# ATMEGA2560_Board_V2.net
KiCad netlist of a schematic drawn in EAGLE
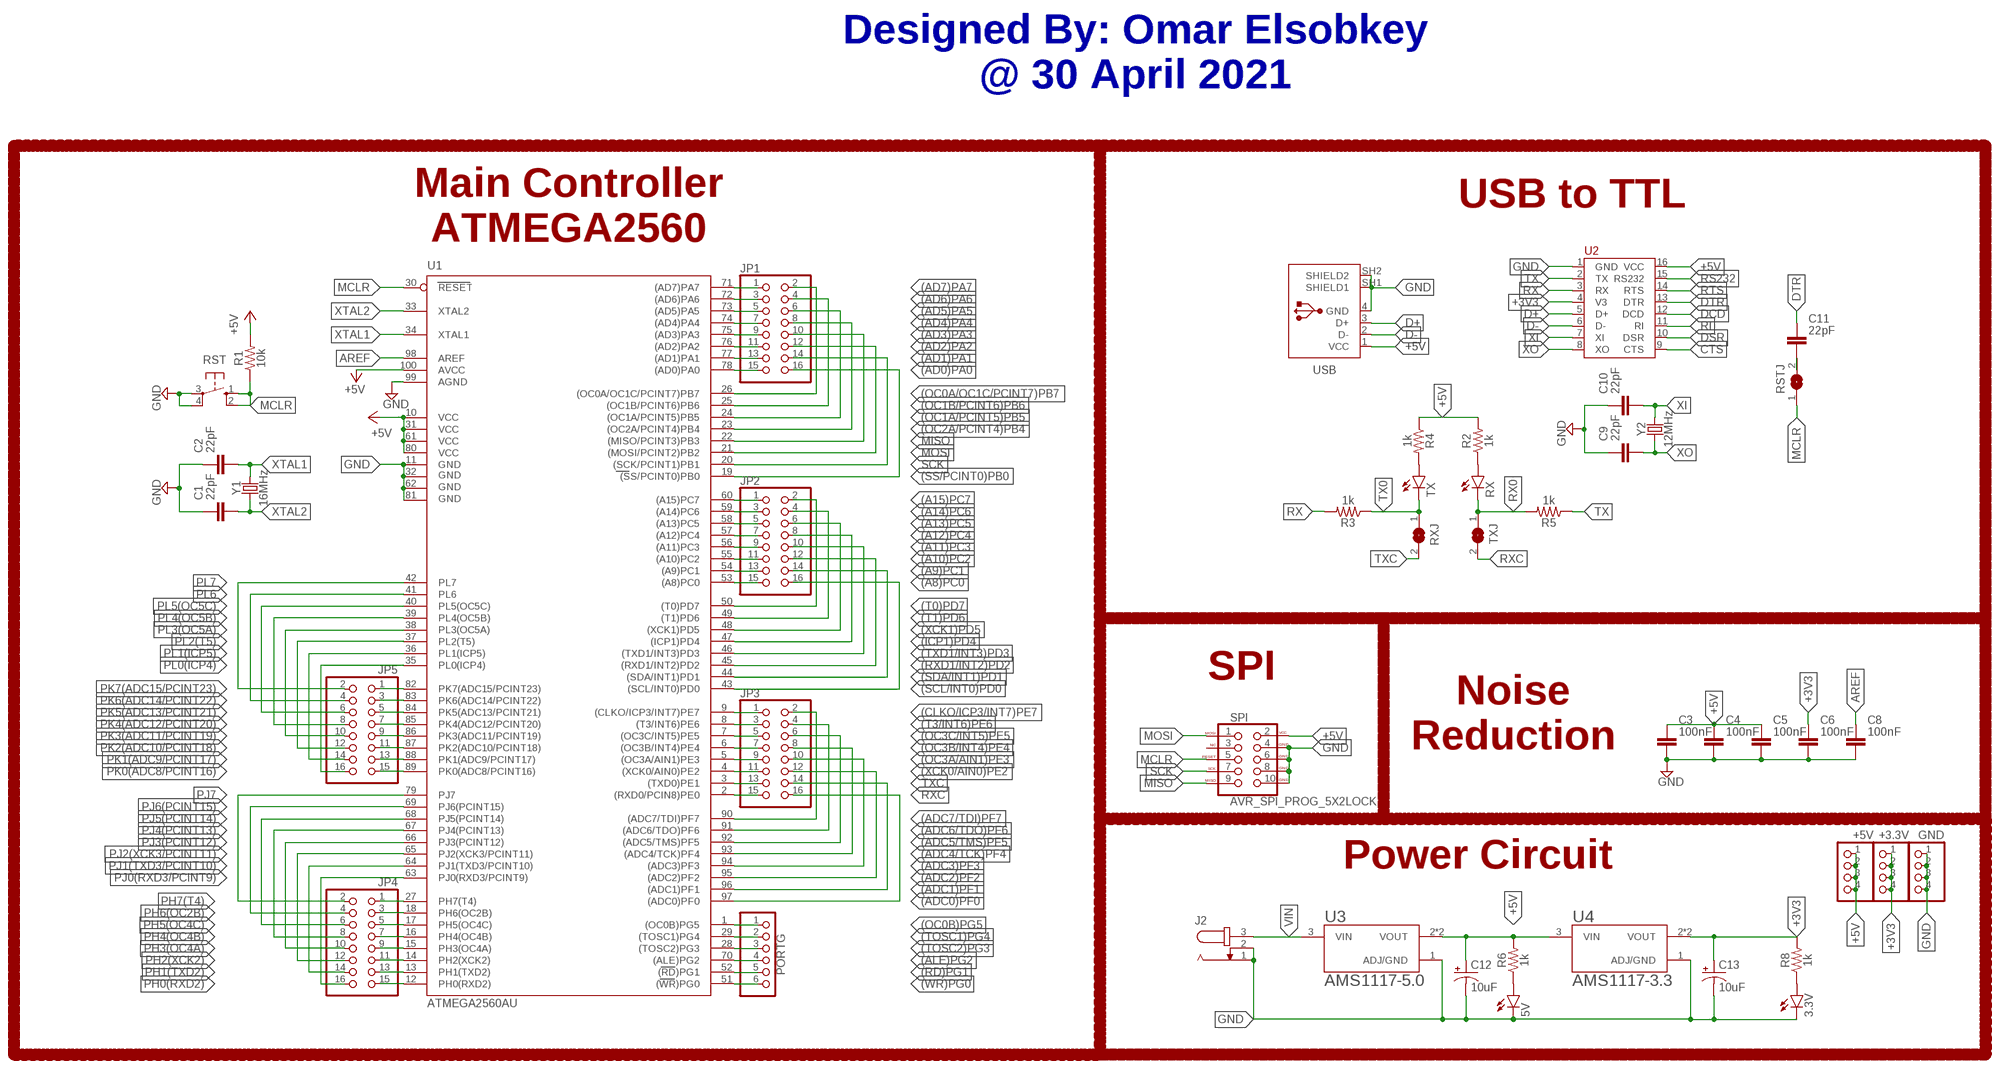
[diagram p0: schematic, sheet 1]

(export (version "E")
  (design (tool "Eeschema 10.0.6"))
  (components
    (comp (ref "+3.3V")
      (value "PINHD-1X4")
      (footprint "eagle-import:1X04")
      (libsource (lib "eagle-import") (part "PINHD-1X4"))
    )
    (comp (ref "+5V")
      (value "PINHD-1X4")
      (footprint "eagle-import:1X04")
      (libsource (lib "eagle-import") (part "PINHD-1X4"))
    )
    (comp (ref "3.3V")
      (value "LEDCHIP-LED0805")
      (footprint "eagle-import:CHIP-LED0805")
      (libsource (lib "eagle-import") (part "LEDCHIP-LED0805"))
    )
    (comp (ref "5V")
      (value "LEDCHIP-LED0805")
      (footprint "eagle-import:CHIP-LED0805")
      (libsource (lib "eagle-import") (part "LEDCHIP-LED0805"))
    )
    (comp (ref "C1")
      (value "22pF")
      (footprint "eagle-import:CAPC2012X110")
      (libsource (lib "eagle-import") (part "CCHIP-0805(2012-METRIC)_"))
    )
    (comp (ref "C2")
      (value "22pF")
      (footprint "eagle-import:CAPC2012X110")
      (libsource (lib "eagle-import") (part "CCHIP-0805(2012-METRIC)_"))
    )
    (comp (ref "C3")
      (value "100nF")
      (footprint "eagle-import:CAPC2012X110")
      (libsource (lib "eagle-import") (part "CCHIP-0805(2012-METRIC)_"))
    )
    (comp (ref "C4")
      (value "100nF")
      (footprint "eagle-import:CAPC2012X110")
      (libsource (lib "eagle-import") (part "CCHIP-0805(2012-METRIC)_"))
    )
    (comp (ref "C5")
      (value "100nF")
      (footprint "eagle-import:CAPC2012X110")
      (libsource (lib "eagle-import") (part "CCHIP-0805(2012-METRIC)_"))
    )
    (comp (ref "C6")
      (value "100nF")
      (footprint "eagle-import:CAPC2012X110")
      (libsource (lib "eagle-import") (part "CCHIP-0805(2012-METRIC)_"))
    )
    (comp (ref "C8")
      (value "100nF")
      (footprint "eagle-import:CAPC2012X110")
      (libsource (lib "eagle-import") (part "CCHIP-0805(2012-METRIC)_"))
    )
    (comp (ref "C9")
      (value "22pF")
      (footprint "eagle-import:CAPC2012X110")
      (libsource (lib "eagle-import") (part "CCHIP-0805(2012-METRIC)_"))
    )
    (comp (ref "C10")
      (value "22pF")
      (footprint "eagle-import:CAPC2012X110")
      (libsource (lib "eagle-import") (part "CCHIP-0805(2012-METRIC)_"))
    )
    (comp (ref "C11")
      (value "22pF")
      (footprint "eagle-import:CAPC2012X110")
      (libsource (lib "eagle-import") (part "CCHIP-0805(2012-METRIC)_"))
    )
    (comp (ref "C12")
      (value "10uF")
      (footprint "eagle-import:CPOL-RADIAL-2.5MM-5MM-KIT")
      (libsource (lib "eagle-import") (part "10UF-POLAR-RADIAL-2.5MM-KIT-25V-20%"))
    )
    (comp (ref "C13")
      (value "10uF")
      (footprint "eagle-import:CPOL-RADIAL-2.5MM-5MM-KIT")
      (libsource (lib "eagle-import") (part "10UF-POLAR-RADIAL-2.5MM-KIT-25V-20%"))
    )
    (comp (ref "GND")
      (value "PINHD-1X4")
      (footprint "eagle-import:1X04")
      (libsource (lib "eagle-import") (part "PINHD-1X4"))
    )
    (comp (ref "J2")
      (value "JACK-PLUG0")
      (footprint "eagle-import:SPC4077")
      (libsource (lib "eagle-import") (part "JACK-PLUG0"))
    )
    (comp (ref "JP1")
      (value "PINHD-2X8")
      (footprint "eagle-import:2X08")
      (libsource (lib "eagle-import") (part "PINHD-2X8"))
    )
    (comp (ref "JP2")
      (value "PINHD-2X8")
      (footprint "eagle-import:2X08")
      (libsource (lib "eagle-import") (part "PINHD-2X8"))
    )
    (comp (ref "JP3")
      (value "PINHD-2X8")
      (footprint "eagle-import:2X08")
      (libsource (lib "eagle-import") (part "PINHD-2X8"))
    )
    (comp (ref "JP4")
      (value "PINHD-2X8")
      (footprint "eagle-import:2X08")
      (libsource (lib "eagle-import") (part "PINHD-2X8"))
    )
    (comp (ref "JP5")
      (value "PINHD-2X8")
      (footprint "eagle-import:2X08")
      (libsource (lib "eagle-import") (part "PINHD-2X8"))
    )
    (comp (ref "PORTG")
      (value "PINHD-1X6")
      (footprint "eagle-import:1X06")
      (libsource (lib "eagle-import") (part "PINHD-1X6"))
    )
    (comp (ref "R1")
      (value "10k")
      (footprint "eagle-import:1206")
      (libsource (lib "eagle-import") (part "RESISTOR1206"))
    )
    (comp (ref "R2")
      (value "1k")
      (footprint "eagle-import:1206")
      (libsource (lib "eagle-import") (part "RESISTOR1206"))
    )
    (comp (ref "R3")
      (value "1k")
      (footprint "eagle-import:1206")
      (libsource (lib "eagle-import") (part "RESISTOR1206"))
    )
    (comp (ref "R4")
      (value "1k")
      (footprint "eagle-import:1206")
      (libsource (lib "eagle-import") (part "RESISTOR1206"))
    )
    (comp (ref "R5")
      (value "1k")
      (footprint "eagle-import:1206")
      (libsource (lib "eagle-import") (part "RESISTOR1206"))
    )
    (comp (ref "R6")
      (value "1k")
      (footprint "eagle-import:1206")
      (libsource (lib "eagle-import") (part "RESISTOR1206"))
    )
    (comp (ref "R8")
      (value "1k")
      (footprint "eagle-import:1206")
      (libsource (lib "eagle-import") (part "RESISTOR1206"))
    )
    (comp (ref "RST")
      (value "10-XX")
      (footprint "eagle-import:B3F-10XX")
      (fields (field (name "MPN") "B3F-1000"))
      (libsource (lib "eagle-import") (part "10-XX"))
    )
    (comp (ref "RSTJ")
      (value "SJW")
      (footprint "eagle-import:SJW")
      (libsource (lib "eagle-import") (part "SJW"))
    )
    (comp (ref "RX")
      (value "LEDCHIP-LED0805")
      (footprint "eagle-import:CHIP-LED0805")
      (libsource (lib "eagle-import") (part "LEDCHIP-LED0805"))
    )
    (comp (ref "RXJ")
      (value "SJW")
      (footprint "eagle-import:SJW")
      (libsource (lib "eagle-import") (part "SJW"))
    )
    (comp (ref "SPI")
      (value "AVR_SPI_PROG_5X2LOCK")
      (footprint "eagle-import:2X5-SHROUDED_LOCK")
      (libsource (lib "eagle-import") (part "AVR_SPI_PROG_5X2LOCK"))
    )
    (comp (ref "TX")
      (value "LEDCHIP-LED0805")
      (footprint "eagle-import:CHIP-LED0805")
      (libsource (lib "eagle-import") (part "LEDCHIP-LED0805"))
    )
    (comp (ref "TXJ")
      (value "SJW")
      (footprint "eagle-import:SJW")
      (libsource (lib "eagle-import") (part "SJW"))
    )
    (comp (ref "U1")
      (value "ATMEGA2560AU")
      (footprint "eagle-import:TQFP100")
      (libsource (lib "eagle-import") (part "ATMEGA2560AU"))
    )
    (comp (ref "U2")
      (value "CH340G")
      (footprint "eagle-import:SOP-16")
      (libsource (lib "eagle-import") (part "CH340G"))
    )
    (comp (ref "U3")
      (value "AMS1117-5.0")
      (footprint "eagle-import:AMS1117-5.0")
      (fields (field (name "MF") "Advanced Monolithic Systems"))
      (libsource (lib "eagle-import") (part "AMS1117-5.0"))
    )
    (comp (ref "U4")
      (value "AMS1117-3.3")
      (footprint "eagle-import:AMS1117-5.0")
      (fields (field (name "MF") "Advanced Monolithic Systems") (field (name "MP") "AMS1117-5.0"))
      (libsource (lib "eagle-import") (part "AMS1117-5.0"))
    )
    (comp (ref "USB")
      (value "61729-1011")
      (footprint "eagle-import:61729-1011BLF")
      (fields (field (name "MANUFACTURER") "Amphenol ICC (FCI)") (field (name "MPN") "61729-1011BLF"))
      (libsource (lib "eagle-import") (part "61729-1011"))
    )
    (comp (ref "Y1")
      (value "16MHz")
      (footprint "eagle-import:HC49U")
      (libsource (lib "eagle-import") (part "CRYSTALPTH-HC49UV"))
    )
    (comp (ref "Y2")
      (value "12MHz")
      (footprint "eagle-import:HC49U")
      (libsource (lib "eagle-import") (part "CRYSTALPTH-HC49UV"))
    )
  )
  (nets
    (net (code "1") (name "(A8)PC0") (class "Default")
      (node (ref "JP2") (pin "15") (pinfunction "15_15") (pintype "passive"))
      (node (ref "U1") (pin "53") (pinfunction "(A8)PC0_53") (pintype "bidirectional"))
    )
    (net (code "2") (name "(A9)PC1") (class "Default")
      (node (ref "JP2") (pin "13") (pinfunction "13_13") (pintype "passive"))
      (node (ref "U1") (pin "54") (pinfunction "(A9)PC1_54") (pintype "bidirectional"))
    )
    (net (code "3") (name "(A10)PC2") (class "Default")
      (node (ref "JP2") (pin "11") (pinfunction "11_11") (pintype "passive"))
      (node (ref "U1") (pin "55") (pinfunction "(A10)PC2_55") (pintype "bidirectional"))
    )
    (net (code "4") (name "(A11)PC3") (class "Default")
      (node (ref "JP2") (pin "9") (pinfunction "9_9") (pintype "passive"))
      (node (ref "U1") (pin "56") (pinfunction "(A11)PC3_56") (pintype "bidirectional"))
    )
    (net (code "5") (name "(A12)PC4") (class "Default")
      (node (ref "JP2") (pin "7") (pinfunction "7_7") (pintype "passive"))
      (node (ref "U1") (pin "57") (pinfunction "(A12)PC4_57") (pintype "bidirectional"))
    )
    (net (code "6") (name "(A13)PC5") (class "Default")
      (node (ref "JP2") (pin "5") (pinfunction "5_5") (pintype "passive"))
      (node (ref "U1") (pin "58") (pinfunction "(A13)PC5_58") (pintype "bidirectional"))
    )
    (net (code "7") (name "(A14)PC6") (class "Default")
      (node (ref "JP2") (pin "3") (pinfunction "3_3") (pintype "passive"))
      (node (ref "U1") (pin "59") (pinfunction "(A14)PC6_59") (pintype "bidirectional"))
    )
    (net (code "8") (name "(A15)PC7") (class "Default")
      (node (ref "JP2") (pin "1") (pinfunction "1_1") (pintype "passive"))
      (node (ref "U1") (pin "60") (pinfunction "(A15)PC7_60") (pintype "bidirectional"))
    )
    (net (code "9") (name "(AD0)PA0") (class "Default")
      (node (ref "JP1") (pin "15") (pinfunction "15_15") (pintype "passive"))
      (node (ref "U1") (pin "78") (pinfunction "(AD0)PA0_78") (pintype "bidirectional"))
    )
    (net (code "10") (name "(AD1)PA1") (class "Default")
      (node (ref "JP1") (pin "13") (pinfunction "13_13") (pintype "passive"))
      (node (ref "U1") (pin "77") (pinfunction "(AD1)PA1_77") (pintype "bidirectional"))
    )
    (net (code "11") (name "(AD2)PA2") (class "Default")
      (node (ref "JP1") (pin "11") (pinfunction "11_11") (pintype "passive"))
      (node (ref "U1") (pin "76") (pinfunction "(AD2)PA2_76") (pintype "bidirectional"))
    )
    (net (code "12") (name "(AD3)PA3") (class "Default")
      (node (ref "JP1") (pin "9") (pinfunction "9_9") (pintype "passive"))
      (node (ref "U1") (pin "75") (pinfunction "(AD3)PA3_75") (pintype "bidirectional"))
    )
    (net (code "13") (name "(AD4)PA4") (class "Default")
      (node (ref "JP1") (pin "7") (pinfunction "7_7") (pintype "passive"))
      (node (ref "U1") (pin "74") (pinfunction "(AD4)PA4_74") (pintype "bidirectional"))
    )
    (net (code "14") (name "(AD5)PA5") (class "Default")
      (node (ref "JP1") (pin "5") (pinfunction "5_5") (pintype "passive"))
      (node (ref "U1") (pin "73") (pinfunction "(AD5)PA5_73") (pintype "bidirectional"))
    )
    (net (code "15") (name "(AD6)PA6") (class "Default")
      (node (ref "JP1") (pin "3") (pinfunction "3_3") (pintype "passive"))
      (node (ref "U1") (pin "72") (pinfunction "(AD6)PA6_72") (pintype "bidirectional"))
    )
    (net (code "16") (name "(AD7)PA7") (class "Default")
      (node (ref "JP1") (pin "1") (pinfunction "1_1") (pintype "passive"))
      (node (ref "U1") (pin "71") (pinfunction "(AD7)PA7_71") (pintype "bidirectional"))
    )
    (net (code "17") (name "(ADC0)PF0") (class "Default")
      (node (ref "JP3") (pin "16") (pinfunction "16_16") (pintype "passive"))
      (node (ref "U1") (pin "97") (pinfunction "(ADC0)PF0_97") (pintype "bidirectional"))
    )
    (net (code "18") (name "(ADC1)PF1") (class "Default")
      (node (ref "JP3") (pin "14") (pinfunction "14_14") (pintype "passive"))
      (node (ref "U1") (pin "96") (pinfunction "(ADC1)PF1_96") (pintype "bidirectional"))
    )
    (net (code "19") (name "(ADC2)PF2") (class "Default")
      (node (ref "JP3") (pin "12") (pinfunction "12_12") (pintype "passive"))
      (node (ref "U1") (pin "95") (pinfunction "(ADC2)PF2_95") (pintype "bidirectional"))
    )
    (net (code "20") (name "(ADC3)PF3") (class "Default")
      (node (ref "JP3") (pin "10") (pinfunction "10_10") (pintype "passive"))
      (node (ref "U1") (pin "94") (pinfunction "(ADC3)PF3_94") (pintype "bidirectional"))
    )
    (net (code "21") (name "(ADC4{slash}TCK)PF4") (class "Default")
      (node (ref "JP3") (pin "8") (pinfunction "8_8") (pintype "passive"))
      (node (ref "U1") (pin "93") (pinfunction "(ADC4/TCK)PF4_93") (pintype "bidirectional"))
    )
    (net (code "22") (name "(ADC5{slash}TMS)PF5") (class "Default")
      (node (ref "JP3") (pin "6") (pinfunction "6_6") (pintype "passive"))
      (node (ref "U1") (pin "92") (pinfunction "(ADC5/TMS)PF5_92") (pintype "bidirectional"))
    )
    (net (code "23") (name "(ADC6{slash}TDO)PF6") (class "Default")
      (node (ref "JP3") (pin "4") (pinfunction "4_4") (pintype "passive"))
      (node (ref "U1") (pin "91") (pinfunction "(ADC6/TDO)PF6_91") (pintype "bidirectional"))
    )
    (net (code "24") (name "(ADC7{slash}TDI)PF7") (class "Default")
      (node (ref "JP3") (pin "2") (pinfunction "2_2") (pintype "passive"))
      (node (ref "U1") (pin "90") (pinfunction "(ADC7/TDI)PF7_90") (pintype "bidirectional"))
    )
    (net (code "25") (name "(ALE)PG2") (class "Default")
      (node (ref "PORTG") (pin "4") (pinfunction "4_4") (pintype "passive"))
      (node (ref "U1") (pin "70") (pinfunction "(ALE)PG2_70") (pintype "bidirectional"))
    )
    (net (code "26") (name "(CLKO{slash}ICP3{slash}INT7)PE7") (class "Default")
      (node (ref "JP3") (pin "1") (pinfunction "1_1") (pintype "passive"))
      (node (ref "U1") (pin "9") (pinfunction "(CLKO/ICP3/INT7)PE7_9") (pintype "bidirectional"))
    )
    (net (code "27") (name "(ICP1)PD4") (class "Default")
      (node (ref "JP2") (pin "8") (pinfunction "8_8") (pintype "passive"))
      (node (ref "U1") (pin "47") (pinfunction "(ICP1)PD4_47") (pintype "bidirectional"))
    )
    (net (code "28") (name "(OC0A{slash}OC1C{slash}PCINT7)PB7") (class "Default")
      (node (ref "JP1") (pin "2") (pinfunction "2_2") (pintype "passive"))
      (node (ref "U1") (pin "26") (pinfunction "(OC0A/OC1C/PCINT7)PB7_26") (pintype "bidirectional"))
    )
    (net (code "29") (name "(OC0B)PG5") (class "Default")
      (node (ref "PORTG") (pin "1") (pinfunction "1_1") (pintype "passive"))
      (node (ref "U1") (pin "1") (pinfunction "(OC0B)PG5_1") (pintype "bidirectional"))
    )
    (net (code "30") (name "(OC1A{slash}PCINT5)PB5") (class "Default")
      (node (ref "JP1") (pin "6") (pinfunction "6_6") (pintype "passive"))
      (node (ref "U1") (pin "24") (pinfunction "(OC1A/PCINT5)PB5_24") (pintype "bidirectional"))
    )
    (net (code "31") (name "(OC1B{slash}PCINT6)PB6") (class "Default")
      (node (ref "JP1") (pin "4") (pinfunction "4_4") (pintype "passive"))
      (node (ref "U1") (pin "25") (pinfunction "(OC1B/PCINT6)PB6_25") (pintype "bidirectional"))
    )
    (net (code "32") (name "(OC2A{slash}PCINT4)PB4") (class "Default")
      (node (ref "JP1") (pin "8") (pinfunction "8_8") (pintype "passive"))
      (node (ref "U1") (pin "23") (pinfunction "(OC2A/PCINT4)PB4_23") (pintype "bidirectional"))
    )
    (net (code "33") (name "(OC3A{slash}AIN1)PE3") (class "Default")
      (node (ref "JP3") (pin "9") (pinfunction "9_9") (pintype "passive"))
      (node (ref "U1") (pin "5") (pinfunction "(OC3A/AIN1)PE3_5") (pintype "bidirectional"))
    )
    (net (code "34") (name "(OC3B{slash}INT4)PE4") (class "Default")
      (node (ref "JP3") (pin "7") (pinfunction "7_7") (pintype "passive"))
      (node (ref "U1") (pin "6") (pinfunction "(OC3B/INT4)PE4_6") (pintype "bidirectional"))
    )
    (net (code "35") (name "(OC3C{slash}INT5)PE5") (class "Default")
      (node (ref "JP3") (pin "5") (pinfunction "5_5") (pintype "passive"))
      (node (ref "U1") (pin "7") (pinfunction "(OC3C/INT5)PE5_7") (pintype "bidirectional"))
    )
    (net (code "36") (name "(RD)PG1") (class "Default")
      (node (ref "PORTG") (pin "5") (pinfunction "5_5") (pintype "passive"))
      (node (ref "U1") (pin "52") (pinfunction "(RD)PG1_52") (pintype "bidirectional"))
    )
    (net (code "37") (name "(RXD1{slash}INT2)PD2") (class "Default")
      (node (ref "JP2") (pin "12") (pinfunction "12_12") (pintype "passive"))
      (node (ref "U1") (pin "45") (pinfunction "(RXD1/INT2)PD2_45") (pintype "bidirectional"))
    )
    (net (code "38") (name "(SCL{slash}INT0)PD0") (class "Default")
      (node (ref "JP2") (pin "16") (pinfunction "16_16") (pintype "passive"))
      (node (ref "U1") (pin "43") (pinfunction "(SCL/INT0)PD0_43") (pintype "bidirectional"))
    )
    (net (code "39") (name "(SDA{slash}INT1)PD1") (class "Default")
      (node (ref "JP2") (pin "14") (pinfunction "14_14") (pintype "passive"))
      (node (ref "U1") (pin "44") (pinfunction "(SDA/INT1)PD1_44") (pintype "bidirectional"))
    )
    (net (code "40") (name "(SS{slash}PCINT0)PB0") (class "Default")
      (node (ref "JP1") (pin "16") (pinfunction "16_16") (pintype "passive"))
      (node (ref "U1") (pin "19") (pinfunction "(SS/PCINT0)PB0_19") (pintype "bidirectional"))
    )
    (net (code "41") (name "(T0)PD7") (class "Default")
      (node (ref "JP2") (pin "2") (pinfunction "2_2") (pintype "passive"))
      (node (ref "U1") (pin "50") (pinfunction "(T0)PD7_50") (pintype "bidirectional"))
    )
    (net (code "42") (name "(T1)PD6") (class "Default")
      (node (ref "JP2") (pin "4") (pinfunction "4_4") (pintype "passive"))
      (node (ref "U1") (pin "49") (pinfunction "(T1)PD6_49") (pintype "bidirectional"))
    )
    (net (code "43") (name "(T3{slash}INT6)PE6") (class "Default")
      (node (ref "JP3") (pin "3") (pinfunction "3_3") (pintype "passive"))
      (node (ref "U1") (pin "8") (pinfunction "(T3/INT6)PE6_8") (pintype "bidirectional"))
    )
    (net (code "44") (name "(TOSC1)PG4") (class "Default")
      (node (ref "PORTG") (pin "2") (pinfunction "2_2") (pintype "passive"))
      (node (ref "U1") (pin "29") (pinfunction "(TOSC1)PG4_29") (pintype "bidirectional"))
    )
    (net (code "45") (name "(TOSC2)PG3") (class "Default")
      (node (ref "PORTG") (pin "3") (pinfunction "3_3") (pintype "passive"))
      (node (ref "U1") (pin "28") (pinfunction "(TOSC2)PG3_28") (pintype "bidirectional"))
    )
    (net (code "46") (name "(TXD1{slash}INT3)PD3") (class "Default")
      (node (ref "JP2") (pin "10") (pinfunction "10_10") (pintype "passive"))
      (node (ref "U1") (pin "46") (pinfunction "(TXD1/INT3)PD3_46") (pintype "bidirectional"))
    )
    (net (code "47") (name "(WR)PG0") (class "Default")
      (node (ref "PORTG") (pin "6") (pinfunction "6_6") (pintype "passive"))
      (node (ref "U1") (pin "51") (pinfunction "(WR)PG0_51") (pintype "bidirectional"))
    )
    (net (code "48") (name "(XCK0{slash}AIN0)PE2") (class "Default")
      (node (ref "JP3") (pin "11") (pinfunction "11_11") (pintype "passive"))
      (node (ref "U1") (pin "4") (pinfunction "(XCK0/AIN0)PE2_4") (pintype "bidirectional"))
    )
    (net (code "49") (name "(XCK1)PD5") (class "Default")
      (node (ref "JP2") (pin "6") (pinfunction "6_6") (pintype "passive"))
      (node (ref "U1") (pin "48") (pinfunction "(XCK1)PD5_48") (pintype "bidirectional"))
    )
    (net (code "50") (name "+3V3") (class "Default")
      (node (ref "+3.3V") (pin "1") (pinfunction "1_1") (pintype "passive"))
      (node (ref "+3.3V") (pin "2") (pinfunction "2_2") (pintype "passive"))
      (node (ref "+3.3V") (pin "3") (pinfunction "3_3") (pintype "passive"))
      (node (ref "+3.3V") (pin "4") (pinfunction "4_4") (pintype "passive"))
      (node (ref "C13") (pin "1") (pinfunction "+_1") (pintype "passive"))
      (node (ref "C6") (pin "1") (pinfunction "1_1") (pintype "passive"))
      (node (ref "R8") (pin "2") (pinfunction "2_2") (pintype "passive"))
      (node (ref "U2") (pin "4") (pinfunction "V3_4") (pintype "bidirectional"))
      (node (ref "U4") (pin "2") (pinfunction "VOUT_2") (pintype "output"))
      (node (ref "U4") (pin "4") (pinfunction "VOUT_4") (pintype "output"))
    )
    (net (code "51") (name "+5V") (class "Default")
      (node (ref "+5V") (pin "1") (pinfunction "1_1") (pintype "passive"))
      (node (ref "+5V") (pin "2") (pinfunction "2_2") (pintype "passive"))
      (node (ref "+5V") (pin "3") (pinfunction "3_3") (pintype "passive"))
      (node (ref "+5V") (pin "4") (pinfunction "4_4") (pintype "passive"))
      (node (ref "C12") (pin "1") (pinfunction "+_1") (pintype "passive"))
      (node (ref "C3") (pin "1") (pinfunction "1_1") (pintype "passive"))
      (node (ref "C4") (pin "1") (pinfunction "1_1") (pintype "passive"))
      (node (ref "C5") (pin "1") (pinfunction "1_1") (pintype "passive"))
      (node (ref "R1") (pin "2") (pinfunction "2_2") (pintype "passive"))
      (node (ref "R2") (pin "2") (pinfunction "2_2") (pintype "passive"))
      (node (ref "R4") (pin "1") (pinfunction "1_1") (pintype "passive"))
      (node (ref "R6") (pin "2") (pinfunction "2_2") (pintype "passive"))
      (node (ref "SPI") (pin "2") (pinfunction "VCC_2") (pintype "power_in"))
      (node (ref "U1") (pin "10") (pinfunction "VCC_10") (pintype "power_in"))
      (node (ref "U1") (pin "100") (pinfunction "AVCC_100") (pintype "power_in"))
      (node (ref "U1") (pin "31") (pinfunction "VCC1_31") (pintype "power_in"))
      (node (ref "U1") (pin "61") (pinfunction "VCC2_61") (pintype "power_in"))
      (node (ref "U1") (pin "80") (pinfunction "VCC3_80") (pintype "power_in"))
      (node (ref "U2") (pin "16") (pinfunction "VCC_16") (pintype "bidirectional"))
      (node (ref "U3") (pin "2") (pinfunction "VOUT_2") (pintype "output"))
      (node (ref "U3") (pin "4") (pinfunction "VOUT_4") (pintype "output"))
      (node (ref "U4") (pin "3") (pinfunction "VIN_3") (pintype "input"))
      (node (ref "USB") (pin "1") (pinfunction "VCC_1") (pintype "power_in"))
    )
    (net (code "52") (name "AREF") (class "Default")
      (node (ref "C8") (pin "1") (pinfunction "1_1") (pintype "passive"))
      (node (ref "U1") (pin "98") (pinfunction "AREF_98") (pintype "bidirectional"))
    )
    (net (code "53") (name "CTS") (class "Default")
      (node (ref "U2") (pin "9") (pinfunction "CTS_9") (pintype "bidirectional"))
    )
    (net (code "54") (name "D+") (class "Default")
      (node (ref "U2") (pin "5") (pinfunction "D+_5") (pintype "bidirectional"))
      (node (ref "USB") (pin "3") (pinfunction "D+_3") (pintype "bidirectional"))
    )
    (net (code "55") (name "D-") (class "Default")
      (node (ref "U2") (pin "6") (pinfunction "D-_6") (pintype "bidirectional"))
      (node (ref "USB") (pin "2") (pinfunction "D-_2") (pintype "bidirectional"))
    )
    (net (code "56") (name "DCD") (class "Default")
      (node (ref "U2") (pin "12") (pinfunction "DCD_12") (pintype "bidirectional"))
    )
    (net (code "57") (name "DSR") (class "Default")
      (node (ref "U2") (pin "10") (pinfunction "DSR_10") (pintype "bidirectional"))
    )
    (net (code "58") (name "DTR") (class "Default")
      (node (ref "C11") (pin "1") (pinfunction "1_1") (pintype "passive"))
      (node (ref "U2") (pin "13") (pinfunction "DTR_13") (pintype "bidirectional"))
    )
    (net (code "59") (name "GND") (class "Default")
      (node (ref "3.3V") (pin "C") (pinfunction "C_C") (pintype "passive"))
      (node (ref "5V") (pin "C") (pinfunction "C_C") (pintype "passive"))
      (node (ref "C1") (pin "1") (pinfunction "1_1") (pintype "passive"))
      (node (ref "C10") (pin "1") (pinfunction "1_1") (pintype "passive"))
      (node (ref "C12") (pin "2") (pinfunction "-_2") (pintype "passive"))
      (node (ref "C13") (pin "2") (pinfunction "-_2") (pintype "passive"))
      (node (ref "C2") (pin "1") (pinfunction "1_1") (pintype "passive"))
      (node (ref "C3") (pin "2") (pinfunction "2_2") (pintype "passive"))
      (node (ref "C4") (pin "2") (pinfunction "2_2") (pintype "passive"))
      (node (ref "C5") (pin "2") (pinfunction "2_2") (pintype "passive"))
      (node (ref "C6") (pin "2") (pinfunction "2_2") (pintype "passive"))
      (node (ref "C8") (pin "2") (pinfunction "2_2") (pintype "passive"))
      (node (ref "C9") (pin "1") (pinfunction "1_1") (pintype "passive"))
      (node (ref "GND") (pin "1") (pinfunction "1_1") (pintype "passive"))
      (node (ref "GND") (pin "2") (pinfunction "2_2") (pintype "passive"))
      (node (ref "GND") (pin "3") (pinfunction "3_3") (pintype "passive"))
      (node (ref "GND") (pin "4") (pinfunction "4_4") (pintype "passive"))
      (node (ref "J2") (pin "1") (pinfunction "1_1") (pintype "passive"))
      (node (ref "J2") (pin "2") (pinfunction "2_2") (pintype "passive"))
      (node (ref "RST") (pin "3") (pinfunction "P_3") (pintype "passive"))
      (node (ref "RST") (pin "4") (pinfunction "P1_4") (pintype "passive"))
      (node (ref "SPI") (pin "10") (pinfunction "GND_10") (pintype "power_in"))
      (node (ref "SPI") (pin "4") (pinfunction "GND_4") (pintype "power_in"))
      (node (ref "SPI") (pin "6") (pinfunction "GND_6") (pintype "power_in"))
      (node (ref "SPI") (pin "8") (pinfunction "GND_8") (pintype "power_in"))
      (node (ref "U1") (pin "11") (pinfunction "GND_11") (pintype "power_in"))
      (node (ref "U1") (pin "32") (pinfunction "GND1_32") (pintype "power_in"))
      (node (ref "U1") (pin "62") (pinfunction "GND2_62") (pintype "power_in"))
      (node (ref "U1") (pin "81") (pinfunction "GND3_81") (pintype "power_in"))
      (node (ref "U1") (pin "99") (pinfunction "AGND_99") (pintype "power_in"))
      (node (ref "U2") (pin "1") (pinfunction "GND_1") (pintype "bidirectional"))
      (node (ref "U3") (pin "1") (pinfunction "ADJ/GND_1") (pintype "power_in"))
      (node (ref "U4") (pin "1") (pinfunction "ADJ/GND_1") (pintype "power_in"))
      (node (ref "USB") (pin "4") (pinfunction "GND_4") (pintype "power_in"))
      (node (ref "USB") (pin "SH1") (pinfunction "SHIELD1_SH1") (pintype "power_in"))
      (node (ref "USB") (pin "SH2") (pinfunction "SHIELD2_SH2") (pintype "power_in"))
    )
    (net (code "60") (name "MCLR") (class "Default")
      (node (ref "R1") (pin "1") (pinfunction "1_1") (pintype "passive"))
      (node (ref "RST") (pin "1") (pinfunction "S_1") (pintype "passive"))
      (node (ref "RST") (pin "2") (pinfunction "S1_2") (pintype "passive"))
      (node (ref "RSTJ") (pin "1") (pinfunction "1_1") (pintype "passive"))
      (node (ref "SPI") (pin "5") (pinfunction "RESET_5") (pintype "passive"))
      (node (ref "U1") (pin "30") (pinfunction "RESET_30") (pintype "input"))
    )
    (net (code "61") (name "MISO") (class "Default")
      (node (ref "JP1") (pin "10") (pinfunction "10_10") (pintype "passive"))
      (node (ref "SPI") (pin "9") (pinfunction "MISO_9") (pintype "passive"))
      (node (ref "U1") (pin "22") (pinfunction "(MISO/PCINT3)PB3_22") (pintype "bidirectional"))
    )
    (net (code "62") (name "MOSI") (class "Default")
      (node (ref "JP1") (pin "12") (pinfunction "12_12") (pintype "passive"))
      (node (ref "SPI") (pin "1") (pinfunction "MOSI_1") (pintype "passive"))
      (node (ref "U1") (pin "21") (pinfunction "(MOSI/PCINT2)PB2_21") (pintype "bidirectional"))
    )
    (net (code "63") (name "Net-(3.3V-PadA)") (class "Default")
      (node (ref "3.3V") (pin "A") (pinfunction "A_A") (pintype "passive"))
      (node (ref "R8") (pin "1") (pinfunction "1_1") (pintype "passive"))
    )
    (net (code "64") (name "Net-(5V-PadA)") (class "Default")
      (node (ref "5V") (pin "A") (pinfunction "A_A") (pintype "passive"))
      (node (ref "R6") (pin "1") (pinfunction "1_1") (pintype "passive"))
    )
    (net (code "65") (name "Net-(C11-Pad2)") (class "Default")
      (node (ref "C11") (pin "2") (pinfunction "2_2") (pintype "passive"))
      (node (ref "RSTJ") (pin "2") (pinfunction "2_2") (pintype "passive"))
    )
    (net (code "66") (name "Net-(R2-Pad1)") (class "Default")
      (node (ref "R2") (pin "1") (pinfunction "1_1") (pintype "passive"))
      (node (ref "RX") (pin "A") (pinfunction "A_A") (pintype "passive"))
    )
    (net (code "67") (name "Net-(R4-Pad2)") (class "Default")
      (node (ref "R4") (pin "2") (pinfunction "2_2") (pintype "passive"))
      (node (ref "TX") (pin "A") (pinfunction "A_A") (pintype "passive"))
    )
    (net (code "68") (name "PH0(RXD2)") (class "Default")
      (node (ref "JP4") (pin "15") (pinfunction "15_15") (pintype "passive"))
      (node (ref "U1") (pin "12") (pinfunction "PH0(RXD2)_12") (pintype "bidirectional"))
    )
    (net (code "69") (name "PH1(TXD2)") (class "Default")
      (node (ref "JP4") (pin "13") (pinfunction "13_13") (pintype "passive"))
      (node (ref "U1") (pin "13") (pinfunction "PH1(TXD2)_13") (pintype "bidirectional"))
    )
    (net (code "70") (name "PH2(XCK2)") (class "Default")
      (node (ref "JP4") (pin "11") (pinfunction "11_11") (pintype "passive"))
      (node (ref "U1") (pin "14") (pinfunction "PH2(XCK2)_14") (pintype "bidirectional"))
    )
    (net (code "71") (name "PH3(OC4A)") (class "Default")
      (node (ref "JP4") (pin "9") (pinfunction "9_9") (pintype "passive"))
      (node (ref "U1") (pin "15") (pinfunction "PH3(OC4A)_15") (pintype "bidirectional"))
    )
    (net (code "72") (name "PH4(OC4B)") (class "Default")
      (node (ref "JP4") (pin "7") (pinfunction "7_7") (pintype "passive"))
      (node (ref "U1") (pin "16") (pinfunction "PH4(OC4B)_16") (pintype "bidirectional"))
    )
    (net (code "73") (name "PH5(OC4C)") (class "Default")
      (node (ref "JP4") (pin "5") (pinfunction "5_5") (pintype "passive"))
      (node (ref "U1") (pin "17") (pinfunction "PH5(OC4C)_17") (pintype "bidirectional"))
    )
    (net (code "74") (name "PH6(OC2B)") (class "Default")
      (node (ref "JP4") (pin "3") (pinfunction "3_3") (pintype "passive"))
      (node (ref "U1") (pin "18") (pinfunction "PH6(OC2B)_18") (pintype "bidirectional"))
    )
    (net (code "75") (name "PH7(T4)") (class "Default")
      (node (ref "JP4") (pin "1") (pinfunction "1_1") (pintype "passive"))
      (node (ref "U1") (pin "27") (pinfunction "PH7(T4)_27") (pintype "bidirectional"))
    )
    (net (code "76") (name "PJ0(RXD3{slash}PCINT9)") (class "Default")
      (node (ref "JP4") (pin "16") (pinfunction "16_16") (pintype "passive"))
      (node (ref "U1") (pin "63") (pinfunction "PJ0(RXD3/PCINT9)_63") (pintype "bidirectional"))
    )
    (net (code "77") (name "PJ1(TXD3{slash}PCINT10)") (class "Default")
      (node (ref "JP4") (pin "14") (pinfunction "14_14") (pintype "passive"))
      (node (ref "U1") (pin "64") (pinfunction "PJ1(TXD3/PCINT10)_64") (pintype "bidirectional"))
    )
    (net (code "78") (name "PJ2(XCK3{slash}PCINT11)") (class "Default")
      (node (ref "JP4") (pin "12") (pinfunction "12_12") (pintype "passive"))
      (node (ref "U1") (pin "65") (pinfunction "PJ2(XCK3/PCINT11)_65") (pintype "bidirectional"))
    )
    (net (code "79") (name "PJ3(PCINT12)") (class "Default")
      (node (ref "JP4") (pin "10") (pinfunction "10_10") (pintype "passive"))
      (node (ref "U1") (pin "66") (pinfunction "PJ3(PCINT12)_66") (pintype "bidirectional"))
    )
    (net (code "80") (name "PJ4(PCINT13)") (class "Default")
      (node (ref "JP4") (pin "8") (pinfunction "8_8") (pintype "passive"))
      (node (ref "U1") (pin "67") (pinfunction "PJ4(PCINT13)_67") (pintype "bidirectional"))
    )
    (net (code "81") (name "PJ5(PCINT14)") (class "Default")
      (node (ref "JP4") (pin "6") (pinfunction "6_6") (pintype "passive"))
      (node (ref "U1") (pin "68") (pinfunction "PJ5(PCINT14)_68") (pintype "bidirectional"))
    )
    (net (code "82") (name "PJ6(PCINT15)") (class "Default")
      (node (ref "JP4") (pin "4") (pinfunction "4_4") (pintype "passive"))
      (node (ref "U1") (pin "69") (pinfunction "PJ6(PCINT15)_69") (pintype "bidirectional"))
    )
    (net (code "83") (name "PJ7") (class "Default")
      (node (ref "JP4") (pin "2") (pinfunction "2_2") (pintype "passive"))
      (node (ref "U1") (pin "79") (pinfunction "PJ7_79") (pintype "bidirectional"))
    )
    (net (code "84") (name "PK0(ADC8{slash}PCINT16)") (class "Default")
      (node (ref "JP5") (pin "15") (pinfunction "15_15") (pintype "passive"))
      (node (ref "U1") (pin "89") (pinfunction "PK0(ADC8/PCINT16)_89") (pintype "bidirectional"))
    )
    (net (code "85") (name "PK1(ADC9{slash}PCINT17)") (class "Default")
      (node (ref "JP5") (pin "13") (pinfunction "13_13") (pintype "passive"))
      (node (ref "U1") (pin "88") (pinfunction "PK1(ADC9/PCINT17)_88") (pintype "bidirectional"))
    )
    (net (code "86") (name "PK2(ADC10{slash}PCINT18)") (class "Default")
      (node (ref "JP5") (pin "11") (pinfunction "11_11") (pintype "passive"))
      (node (ref "U1") (pin "87") (pinfunction "PK2(ADC10/PCINT18)_87") (pintype "bidirectional"))
    )
    (net (code "87") (name "PK3(ADC11{slash}PCINT19)") (class "Default")
      (node (ref "JP5") (pin "9") (pinfunction "9_9") (pintype "passive"))
      (node (ref "U1") (pin "86") (pinfunction "PK3(ADC11/PCINT19)_86") (pintype "bidirectional"))
    )
    (net (code "88") (name "PK4(ADC12{slash}PCINT20)") (class "Default")
      (node (ref "JP5") (pin "7") (pinfunction "7_7") (pintype "passive"))
      (node (ref "U1") (pin "85") (pinfunction "PK4(ADC12/PCINT20)_85") (pintype "bidirectional"))
    )
    (net (code "89") (name "PK5(ADC13{slash}PCINT21)") (class "Default")
      (node (ref "JP5") (pin "5") (pinfunction "5_5") (pintype "passive"))
      (node (ref "U1") (pin "84") (pinfunction "PK5(ADC13/PCINT21)_84") (pintype "bidirectional"))
    )
    (net (code "90") (name "PK6(ADC14{slash}PCINT22)") (class "Default")
      (node (ref "JP5") (pin "3") (pinfunction "3_3") (pintype "passive"))
      (node (ref "U1") (pin "83") (pinfunction "PK6(ADC14/PCINT22)_83") (pintype "bidirectional"))
    )
    (net (code "91") (name "PK7(ADC15{slash}PCINT23)") (class "Default")
      (node (ref "JP5") (pin "1") (pinfunction "1_1") (pintype "passive"))
      (node (ref "U1") (pin "82") (pinfunction "PK7(ADC15/PCINT23)_82") (pintype "bidirectional"))
    )
    (net (code "92") (name "PL0(ICP4)") (class "Default")
      (node (ref "JP5") (pin "16") (pinfunction "16_16") (pintype "passive"))
      (node (ref "U1") (pin "35") (pinfunction "PL0(ICP4)_35") (pintype "bidirectional"))
    )
    (net (code "93") (name "PL1(ICP5)") (class "Default")
      (node (ref "JP5") (pin "14") (pinfunction "14_14") (pintype "passive"))
      (node (ref "U1") (pin "36") (pinfunction "PL1(ICP5)_36") (pintype "bidirectional"))
    )
    (net (code "94") (name "PL2(T5)") (class "Default")
      (node (ref "JP5") (pin "12") (pinfunction "12_12") (pintype "passive"))
      (node (ref "U1") (pin "37") (pinfunction "PL2(T5)_37") (pintype "bidirectional"))
    )
    (net (code "95") (name "PL3(OC5A)") (class "Default")
      (node (ref "JP5") (pin "10") (pinfunction "10_10") (pintype "passive"))
      (node (ref "U1") (pin "38") (pinfunction "PL3(OC5A)_38") (pintype "bidirectional"))
    )
    (net (code "96") (name "PL4(OC5B)") (class "Default")
      (node (ref "JP5") (pin "8") (pinfunction "8_8") (pintype "passive"))
      (node (ref "U1") (pin "39") (pinfunction "PL4(OC5B)_39") (pintype "bidirectional"))
    )
    (net (code "97") (name "PL5(OC5C)") (class "Default")
      (node (ref "JP5") (pin "6") (pinfunction "6_6") (pintype "passive"))
      (node (ref "U1") (pin "40") (pinfunction "PL5(OC5C)_40") (pintype "bidirectional"))
    )
    (net (code "98") (name "PL6") (class "Default")
      (node (ref "JP5") (pin "4") (pinfunction "4_4") (pintype "passive"))
      (node (ref "U1") (pin "41") (pinfunction "PL6_41") (pintype "bidirectional"))
    )
    (net (code "99") (name "PL7") (class "Default")
      (node (ref "JP5") (pin "2") (pinfunction "2_2") (pintype "passive"))
      (node (ref "U1") (pin "42") (pinfunction "PL7_42") (pintype "bidirectional"))
    )
    (net (code "100") (name "RI") (class "Default")
      (node (ref "U2") (pin "11") (pinfunction "RI_11") (pintype "bidirectional"))
    )
    (net (code "101") (name "RS232") (class "Default")
      (node (ref "U2") (pin "15") (pinfunction "RS232_15") (pintype "bidirectional"))
    )
    (net (code "102") (name "RTS") (class "Default")
      (node (ref "U2") (pin "14") (pinfunction "RTS_14") (pintype "bidirectional"))
    )
    (net (code "103") (name "RX") (class "Default")
      (node (ref "R3") (pin "2") (pinfunction "2_2") (pintype "passive"))
      (node (ref "U2") (pin "3") (pinfunction "RX_3") (pintype "bidirectional"))
    )
    (net (code "104") (name "RX0") (class "Default")
      (node (ref "R5") (pin "2") (pinfunction "2_2") (pintype "passive"))
      (node (ref "RX") (pin "C") (pinfunction "C_C") (pintype "passive"))
      (node (ref "TXJ") (pin "1") (pinfunction "1_1") (pintype "passive"))
    )
    (net (code "105") (name "RXC") (class "Default")
      (node (ref "JP3") (pin "15") (pinfunction "15_15") (pintype "passive"))
      (node (ref "TXJ") (pin "2") (pinfunction "2_2") (pintype "passive"))
      (node (ref "U1") (pin "2") (pinfunction "(RXD0/PCIN8)PE0_2") (pintype "bidirectional"))
    )
    (net (code "106") (name "SCK") (class "Default")
      (node (ref "JP1") (pin "14") (pinfunction "14_14") (pintype "passive"))
      (node (ref "SPI") (pin "7") (pinfunction "SCK_7") (pintype "passive"))
      (node (ref "U1") (pin "20") (pinfunction "(SCK/PCINT1)PB1_20") (pintype "bidirectional"))
    )
    (net (code "107") (name "TX") (class "Default")
      (node (ref "R5") (pin "1") (pinfunction "1_1") (pintype "passive"))
      (node (ref "U2") (pin "2") (pinfunction "TX_2") (pintype "bidirectional"))
    )
    (net (code "108") (name "TX0") (class "Default")
      (node (ref "R3") (pin "1") (pinfunction "1_1") (pintype "passive"))
      (node (ref "RXJ") (pin "1") (pinfunction "1_1") (pintype "passive"))
      (node (ref "TX") (pin "C") (pinfunction "C_C") (pintype "passive"))
    )
    (net (code "109") (name "TXC") (class "Default")
      (node (ref "JP3") (pin "13") (pinfunction "13_13") (pintype "passive"))
      (node (ref "RXJ") (pin "2") (pinfunction "2_2") (pintype "passive"))
      (node (ref "U1") (pin "3") (pinfunction "(TXD0)PE1_3") (pintype "bidirectional"))
    )
    (net (code "110") (name "VIN") (class "Default")
      (node (ref "J2") (pin "3") (pinfunction "3_3") (pintype "passive"))
      (node (ref "U3") (pin "3") (pinfunction "VIN_3") (pintype "input"))
    )
    (net (code "111") (name "XI") (class "Default")
      (node (ref "C10") (pin "2") (pinfunction "2_2") (pintype "passive"))
      (node (ref "U2") (pin "7") (pinfunction "XI_7") (pintype "bidirectional"))
      (node (ref "Y2") (pin "2") (pinfunction "2_2") (pintype "passive"))
    )
    (net (code "112") (name "XO") (class "Default")
      (node (ref "C9") (pin "2") (pinfunction "2_2") (pintype "passive"))
      (node (ref "U2") (pin "8") (pinfunction "XO_8") (pintype "bidirectional"))
      (node (ref "Y2") (pin "1") (pinfunction "1_1") (pintype "passive"))
    )
    (net (code "113") (name "XTAL1") (class "Default")
      (node (ref "C2") (pin "2") (pinfunction "2_2") (pintype "passive"))
      (node (ref "U1") (pin "34") (pinfunction "XTAL1_34") (pintype "input"))
      (node (ref "Y1") (pin "2") (pinfunction "2_2") (pintype "passive"))
    )
    (net (code "114") (name "XTAL2") (class "Default")
      (node (ref "C1") (pin "2") (pinfunction "2_2") (pintype "passive"))
      (node (ref "U1") (pin "33") (pinfunction "XTAL2_33") (pintype "output"))
      (node (ref "Y1") (pin "1") (pinfunction "1_1") (pintype "passive"))
    )
    (net (code "115") (name "unconnected-(SPI-NC-Pad3)") (class "Default")
      (node (ref "SPI") (pin "3") (pinfunction "NC_3") (pintype "no_connect"))
    )
  )
)
